# PiHatSandwich-v1.net
KiCad netlist of a schematic drawn in EAGLE
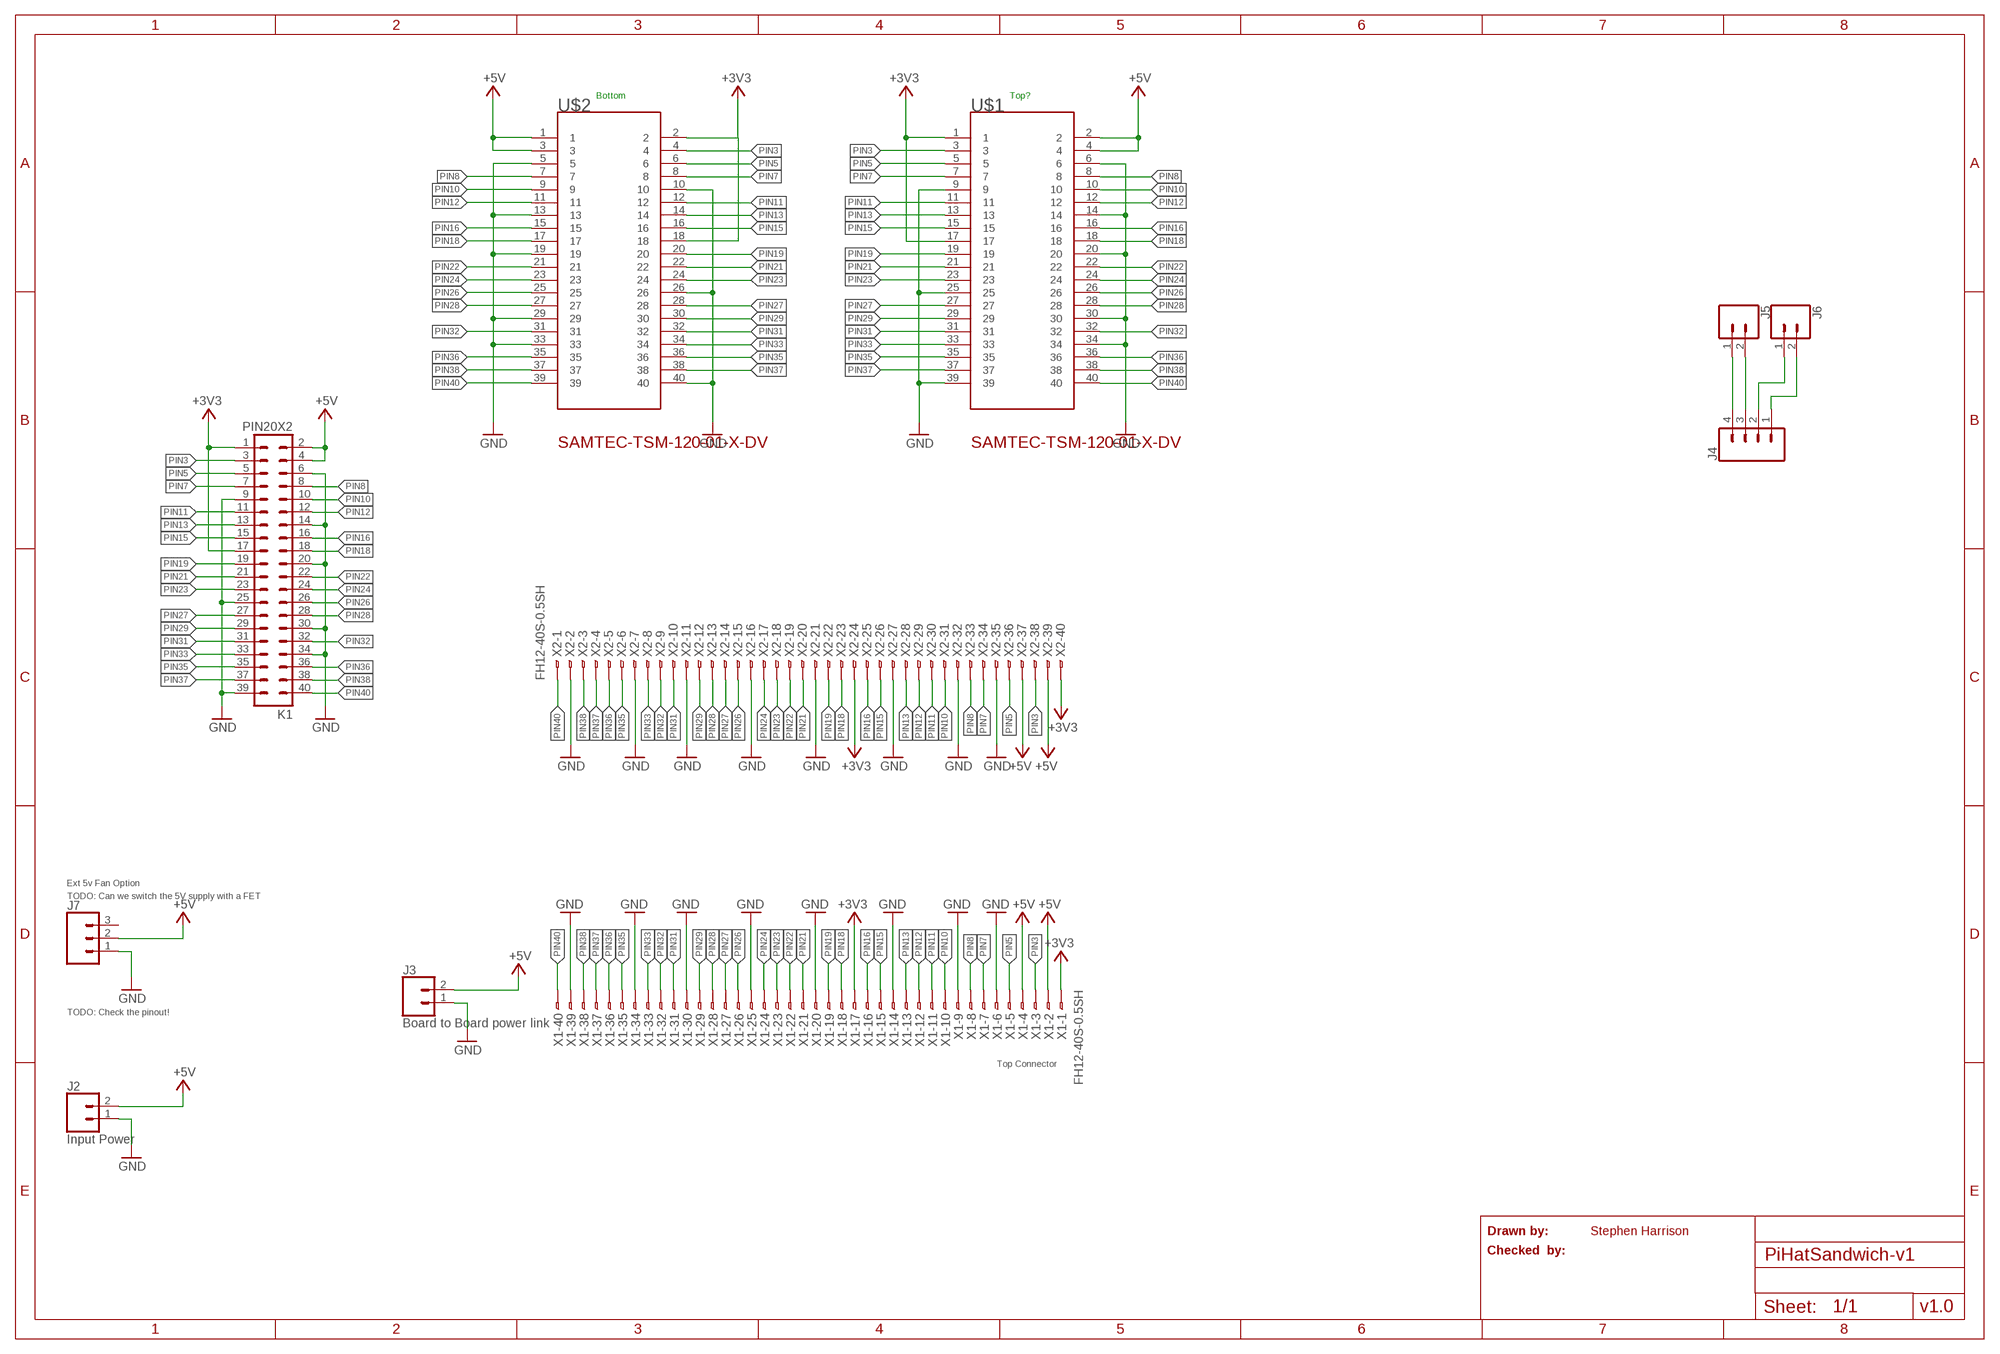
[diagram p0: schematic, sheet 1]

(export (version "E")
  (design (tool "Eeschema 10.0.6"))
  (components
    (comp (ref "J2")
      (value "Input Power")
      (footprint "eagle-import:MOLEX-1X2")
      (libsource (lib "eagle-import") (part "CONN_02POLAR"))
    )
    (comp (ref "J3")
      (value "Board to Board power link")
      (footprint "eagle-import:MOLEX-1X2")
      (libsource (lib "eagle-import") (part "CONN_02POLAR"))
    )
    (comp (ref "J4")
      (value "CONN_04POLAR")
      (footprint "eagle-import:MOLEX-1X4")
      (libsource (lib "eagle-import") (part "CONN_04POLAR"))
    )
    (comp (ref "J5")
      (value "CONN_02")
      (footprint "eagle-import:1X02")
      (libsource (lib "eagle-import") (part "CONN_02"))
    )
    (comp (ref "J6")
      (value "CONN_02")
      (footprint "eagle-import:1X02")
      (libsource (lib "eagle-import") (part "CONN_02"))
    )
    (comp (ref "J7")
      (value "CONN_03POLAR")
      (footprint "eagle-import:MOLEX-1X3")
      (libsource (lib "eagle-import") (part "CONN_03POLAR"))
    )
    (comp (ref "K1")
      (value "PIN20X2")
      (footprint "eagle-import:PIN_20X2")
      (libsource (lib "eagle-import") (part "PIN20X2"))
    )
    (comp (ref "U$1")
      (value "SAMTEC-TSM-120-01-X-DVJ")
      (footprint "eagle-import:SAMTEC-TSM-120-01-X-DV")
      (fields (field (name "MF") "Samtec") (field (name "MP") "TSM-120-01-S-DV-M"))
      (libsource (lib "eagle-import") (part "SAMTEC-TSM-120-01-X-DVJ"))
    )
    (comp (ref "U$2")
      (value "SAMTEC-TSM-120-01-X-DVJ")
      (footprint "eagle-import:SAMTEC-TSM-120-01-X-DV")
      (fields (field (name "MF") "Samtec") (field (name "MP") "TSM-120-01-S-DV-M"))
      (libsource (lib "eagle-import") (part "SAMTEC-TSM-120-01-X-DVJ"))
    )
    (comp (ref "X1")
      (value "FH12-40S-0.5SH")
      (footprint "eagle-import:FH12-40S-0.5SH")
      (fields (field (name "MPN") "FH12-40S-0.5SH(55)"))
      (libsource (lib "eagle-import") (part "FH12-40S-0.5SH"))
    )
    (comp (ref "X2")
      (value "FH12-40S-0.5SH")
      (footprint "eagle-import:FH12-40S-0.5SH")
      (fields (field (name "MPN") "FH12-40S-0.5SH(55)"))
      (libsource (lib "eagle-import") (part "FH12-40S-0.5SH"))
    )
  )
  (nets
    (net (code "1") (name "+3V3") (class "Default")
      (node (ref "K1") (pin "1") (pinfunction "1_1") (pintype "passive"))
      (node (ref "K1") (pin "17") (pinfunction "17_17") (pintype "passive"))
      (node (ref "U$1") (pin "1") (pinfunction "1_1") (pintype "passive"))
      (node (ref "U$1") (pin "17") (pinfunction "17_17") (pintype "passive"))
      (node (ref "U$2") (pin "18") (pinfunction "18_18") (pintype "passive"))
      (node (ref "U$2") (pin "2") (pinfunction "2_2") (pintype "passive"))
      (node (ref "X1") (pin "1") (pinfunction "1_1") (pintype "passive"))
      (node (ref "X1") (pin "17") (pinfunction "1_17") (pintype "passive"))
      (node (ref "X2") (pin "24") (pinfunction "1_24") (pintype "passive"))
      (node (ref "X2") (pin "40") (pinfunction "1_40") (pintype "passive"))
    )
    (net (code "2") (name "+5V") (class "Default")
      (node (ref "J2") (pin "2") (pinfunction "2_2") (pintype "passive"))
      (node (ref "J3") (pin "2") (pinfunction "2_2") (pintype "passive"))
      (node (ref "J7") (pin "2") (pinfunction "2_2") (pintype "passive"))
      (node (ref "K1") (pin "2") (pinfunction "2_2") (pintype "passive"))
      (node (ref "K1") (pin "4") (pinfunction "4_4") (pintype "passive"))
      (node (ref "U$1") (pin "2") (pinfunction "2_2") (pintype "passive"))
      (node (ref "U$1") (pin "4") (pinfunction "4_4") (pintype "passive"))
      (node (ref "U$2") (pin "1") (pinfunction "1_1") (pintype "passive"))
      (node (ref "U$2") (pin "3") (pinfunction "3_3") (pintype "passive"))
      (node (ref "X1") (pin "2") (pinfunction "1_2") (pintype "passive"))
      (node (ref "X1") (pin "4") (pinfunction "1_4") (pintype "passive"))
      (node (ref "X2") (pin "37") (pinfunction "1_37") (pintype "passive"))
      (node (ref "X2") (pin "39") (pinfunction "1_39") (pintype "passive"))
    )
    (net (code "3") (name "GND") (class "Default")
      (node (ref "J2") (pin "1") (pinfunction "1_1") (pintype "passive"))
      (node (ref "J3") (pin "1") (pinfunction "1_1") (pintype "passive"))
      (node (ref "J7") (pin "1") (pinfunction "1_1") (pintype "passive"))
      (node (ref "K1") (pin "14") (pinfunction "14_14") (pintype "passive"))
      (node (ref "K1") (pin "20") (pinfunction "20_20") (pintype "passive"))
      (node (ref "K1") (pin "25") (pinfunction "25_25") (pintype "passive"))
      (node (ref "K1") (pin "30") (pinfunction "30_30") (pintype "passive"))
      (node (ref "K1") (pin "34") (pinfunction "34_34") (pintype "passive"))
      (node (ref "K1") (pin "39") (pinfunction "39_39") (pintype "passive"))
      (node (ref "K1") (pin "6") (pinfunction "6_6") (pintype "passive"))
      (node (ref "K1") (pin "9") (pinfunction "9_9") (pintype "passive"))
      (node (ref "U$1") (pin "14") (pinfunction "14_14") (pintype "passive"))
      (node (ref "U$1") (pin "20") (pinfunction "20_20") (pintype "passive"))
      (node (ref "U$1") (pin "25") (pinfunction "25_25") (pintype "passive"))
      (node (ref "U$1") (pin "30") (pinfunction "30_30") (pintype "passive"))
      (node (ref "U$1") (pin "34") (pinfunction "34_34") (pintype "passive"))
      (node (ref "U$1") (pin "39") (pinfunction "39_39") (pintype "passive"))
      (node (ref "U$1") (pin "6") (pinfunction "6_6") (pintype "passive"))
      (node (ref "U$1") (pin "9") (pinfunction "9_9") (pintype "passive"))
      (node (ref "U$2") (pin "10") (pinfunction "10_10") (pintype "passive"))
      (node (ref "U$2") (pin "13") (pinfunction "13_13") (pintype "passive"))
      (node (ref "U$2") (pin "19") (pinfunction "19_19") (pintype "passive"))
      (node (ref "U$2") (pin "26") (pinfunction "26_26") (pintype "passive"))
      (node (ref "U$2") (pin "29") (pinfunction "29_29") (pintype "passive"))
      (node (ref "U$2") (pin "33") (pinfunction "33_33") (pintype "passive"))
      (node (ref "U$2") (pin "40") (pinfunction "40_40") (pintype "passive"))
      (node (ref "U$2") (pin "5") (pinfunction "5_5") (pintype "passive"))
      (node (ref "X1") (pin "14") (pinfunction "1_14") (pintype "passive"))
      (node (ref "X1") (pin "20") (pinfunction "1_20") (pintype "passive"))
      (node (ref "X1") (pin "25") (pinfunction "1_25") (pintype "passive"))
      (node (ref "X1") (pin "30") (pinfunction "1_30") (pintype "passive"))
      (node (ref "X1") (pin "34") (pinfunction "1_34") (pintype "passive"))
      (node (ref "X1") (pin "39") (pinfunction "1_39") (pintype "passive"))
      (node (ref "X1") (pin "6") (pinfunction "1_6") (pintype "passive"))
      (node (ref "X1") (pin "9") (pinfunction "1_9") (pintype "passive"))
      (node (ref "X2") (pin "11") (pinfunction "1_11") (pintype "passive"))
      (node (ref "X2") (pin "16") (pinfunction "1_16") (pintype "passive"))
      (node (ref "X2") (pin "2") (pinfunction "1_2") (pintype "passive"))
      (node (ref "X2") (pin "21") (pinfunction "1_21") (pintype "passive"))
      (node (ref "X2") (pin "27") (pinfunction "1_27") (pintype "passive"))
      (node (ref "X2") (pin "32") (pinfunction "1_32") (pintype "passive"))
      (node (ref "X2") (pin "35") (pinfunction "1_35") (pintype "passive"))
      (node (ref "X2") (pin "7") (pinfunction "1_7") (pintype "passive"))
    )
    (net (code "4") (name "Net-(J4-Pad1)") (class "Default")
      (node (ref "J4") (pin "1") (pinfunction "1_1") (pintype "passive"))
      (node (ref "J6") (pin "2") (pinfunction "2_2") (pintype "passive"))
    )
    (net (code "5") (name "Net-(J4-Pad2)") (class "Default")
      (node (ref "J4") (pin "2") (pinfunction "2_2") (pintype "passive"))
      (node (ref "J6") (pin "1") (pinfunction "1_1") (pintype "passive"))
    )
    (net (code "6") (name "Net-(J4-Pad3)") (class "Default")
      (node (ref "J4") (pin "3") (pinfunction "3_3") (pintype "passive"))
      (node (ref "J5") (pin "2") (pinfunction "2_2") (pintype "passive"))
    )
    (net (code "7") (name "Net-(J4-Pad4)") (class "Default")
      (node (ref "J4") (pin "4") (pinfunction "4_4") (pintype "passive"))
      (node (ref "J5") (pin "1") (pinfunction "1_1") (pintype "passive"))
    )
    (net (code "8") (name "PIN3") (class "Default")
      (node (ref "K1") (pin "3") (pinfunction "3_3") (pintype "passive"))
      (node (ref "U$1") (pin "3") (pinfunction "3_3") (pintype "passive"))
      (node (ref "U$2") (pin "4") (pinfunction "4_4") (pintype "passive"))
      (node (ref "X1") (pin "3") (pinfunction "1_3") (pintype "passive"))
      (node (ref "X2") (pin "38") (pinfunction "1_38") (pintype "passive"))
    )
    (net (code "9") (name "PIN5") (class "Default")
      (node (ref "K1") (pin "5") (pinfunction "5_5") (pintype "passive"))
      (node (ref "U$1") (pin "5") (pinfunction "5_5") (pintype "passive"))
      (node (ref "U$2") (pin "6") (pinfunction "6_6") (pintype "passive"))
      (node (ref "X1") (pin "5") (pinfunction "1_5") (pintype "passive"))
      (node (ref "X2") (pin "36") (pinfunction "1_36") (pintype "passive"))
    )
    (net (code "10") (name "PIN7") (class "Default")
      (node (ref "K1") (pin "7") (pinfunction "7_7") (pintype "passive"))
      (node (ref "U$1") (pin "7") (pinfunction "7_7") (pintype "passive"))
      (node (ref "U$2") (pin "8") (pinfunction "8_8") (pintype "passive"))
      (node (ref "X1") (pin "7") (pinfunction "1_7") (pintype "passive"))
      (node (ref "X2") (pin "34") (pinfunction "1_34") (pintype "passive"))
    )
    (net (code "11") (name "PIN8") (class "Default")
      (node (ref "K1") (pin "8") (pinfunction "8_8") (pintype "passive"))
      (node (ref "U$1") (pin "8") (pinfunction "8_8") (pintype "passive"))
      (node (ref "U$2") (pin "7") (pinfunction "7_7") (pintype "passive"))
      (node (ref "X1") (pin "8") (pinfunction "1_8") (pintype "passive"))
      (node (ref "X2") (pin "33") (pinfunction "1_33") (pintype "passive"))
    )
    (net (code "12") (name "PIN10") (class "Default")
      (node (ref "K1") (pin "10") (pinfunction "10_10") (pintype "passive"))
      (node (ref "U$1") (pin "10") (pinfunction "10_10") (pintype "passive"))
      (node (ref "U$2") (pin "9") (pinfunction "9_9") (pintype "passive"))
      (node (ref "X1") (pin "10") (pinfunction "1_10") (pintype "passive"))
      (node (ref "X2") (pin "31") (pinfunction "1_31") (pintype "passive"))
    )
    (net (code "13") (name "PIN11") (class "Default")
      (node (ref "K1") (pin "11") (pinfunction "11_11") (pintype "passive"))
      (node (ref "U$1") (pin "11") (pinfunction "11_11") (pintype "passive"))
      (node (ref "U$2") (pin "12") (pinfunction "12_12") (pintype "passive"))
      (node (ref "X1") (pin "11") (pinfunction "1_11") (pintype "passive"))
      (node (ref "X2") (pin "30") (pinfunction "1_30") (pintype "passive"))
    )
    (net (code "14") (name "PIN12") (class "Default")
      (node (ref "K1") (pin "12") (pinfunction "12_12") (pintype "passive"))
      (node (ref "U$1") (pin "12") (pinfunction "12_12") (pintype "passive"))
      (node (ref "U$2") (pin "11") (pinfunction "11_11") (pintype "passive"))
      (node (ref "X1") (pin "12") (pinfunction "1_12") (pintype "passive"))
      (node (ref "X2") (pin "29") (pinfunction "1_29") (pintype "passive"))
    )
    (net (code "15") (name "PIN13") (class "Default")
      (node (ref "K1") (pin "13") (pinfunction "13_13") (pintype "passive"))
      (node (ref "U$1") (pin "13") (pinfunction "13_13") (pintype "passive"))
      (node (ref "U$2") (pin "14") (pinfunction "14_14") (pintype "passive"))
      (node (ref "X1") (pin "13") (pinfunction "1_13") (pintype "passive"))
      (node (ref "X2") (pin "28") (pinfunction "1_28") (pintype "passive"))
    )
    (net (code "16") (name "PIN15") (class "Default")
      (node (ref "K1") (pin "15") (pinfunction "15_15") (pintype "passive"))
      (node (ref "U$1") (pin "15") (pinfunction "15_15") (pintype "passive"))
      (node (ref "U$2") (pin "16") (pinfunction "16_16") (pintype "passive"))
      (node (ref "X1") (pin "15") (pinfunction "1_15") (pintype "passive"))
      (node (ref "X2") (pin "26") (pinfunction "1_26") (pintype "passive"))
    )
    (net (code "17") (name "PIN16") (class "Default")
      (node (ref "K1") (pin "16") (pinfunction "16_16") (pintype "passive"))
      (node (ref "U$1") (pin "16") (pinfunction "16_16") (pintype "passive"))
      (node (ref "U$2") (pin "15") (pinfunction "15_15") (pintype "passive"))
      (node (ref "X1") (pin "16") (pinfunction "1_16") (pintype "passive"))
      (node (ref "X2") (pin "25") (pinfunction "1_25") (pintype "passive"))
    )
    (net (code "18") (name "PIN18") (class "Default")
      (node (ref "K1") (pin "18") (pinfunction "18_18") (pintype "passive"))
      (node (ref "U$1") (pin "18") (pinfunction "18_18") (pintype "passive"))
      (node (ref "U$2") (pin "17") (pinfunction "17_17") (pintype "passive"))
      (node (ref "X1") (pin "18") (pinfunction "1_18") (pintype "passive"))
      (node (ref "X2") (pin "23") (pinfunction "1_23") (pintype "passive"))
    )
    (net (code "19") (name "PIN19") (class "Default")
      (node (ref "K1") (pin "19") (pinfunction "19_19") (pintype "passive"))
      (node (ref "U$1") (pin "19") (pinfunction "19_19") (pintype "passive"))
      (node (ref "U$2") (pin "20") (pinfunction "20_20") (pintype "passive"))
      (node (ref "X1") (pin "19") (pinfunction "1_19") (pintype "passive"))
      (node (ref "X2") (pin "22") (pinfunction "1_22") (pintype "passive"))
    )
    (net (code "20") (name "PIN21") (class "Default")
      (node (ref "K1") (pin "21") (pinfunction "21_21") (pintype "passive"))
      (node (ref "U$1") (pin "21") (pinfunction "21_21") (pintype "passive"))
      (node (ref "U$2") (pin "22") (pinfunction "22_22") (pintype "passive"))
      (node (ref "X1") (pin "21") (pinfunction "1_21") (pintype "passive"))
      (node (ref "X2") (pin "20") (pinfunction "1_20") (pintype "passive"))
    )
    (net (code "21") (name "PIN22") (class "Default")
      (node (ref "K1") (pin "22") (pinfunction "22_22") (pintype "passive"))
      (node (ref "U$1") (pin "22") (pinfunction "22_22") (pintype "passive"))
      (node (ref "U$2") (pin "21") (pinfunction "21_21") (pintype "passive"))
      (node (ref "X1") (pin "22") (pinfunction "1_22") (pintype "passive"))
      (node (ref "X2") (pin "19") (pinfunction "1_19") (pintype "passive"))
    )
    (net (code "22") (name "PIN23") (class "Default")
      (node (ref "K1") (pin "23") (pinfunction "23_23") (pintype "passive"))
      (node (ref "U$1") (pin "23") (pinfunction "23_23") (pintype "passive"))
      (node (ref "U$2") (pin "24") (pinfunction "24_24") (pintype "passive"))
      (node (ref "X1") (pin "23") (pinfunction "1_23") (pintype "passive"))
      (node (ref "X2") (pin "18") (pinfunction "1_18") (pintype "passive"))
    )
    (net (code "23") (name "PIN24") (class "Default")
      (node (ref "K1") (pin "24") (pinfunction "24_24") (pintype "passive"))
      (node (ref "U$1") (pin "24") (pinfunction "24_24") (pintype "passive"))
      (node (ref "U$2") (pin "23") (pinfunction "23_23") (pintype "passive"))
      (node (ref "X1") (pin "24") (pinfunction "1_24") (pintype "passive"))
      (node (ref "X2") (pin "17") (pinfunction "1_17") (pintype "passive"))
    )
    (net (code "24") (name "PIN26") (class "Default")
      (node (ref "K1") (pin "26") (pinfunction "26_26") (pintype "passive"))
      (node (ref "U$1") (pin "26") (pinfunction "26_26") (pintype "passive"))
      (node (ref "U$2") (pin "25") (pinfunction "25_25") (pintype "passive"))
      (node (ref "X1") (pin "26") (pinfunction "1_26") (pintype "passive"))
      (node (ref "X2") (pin "15") (pinfunction "1_15") (pintype "passive"))
    )
    (net (code "25") (name "PIN27") (class "Default")
      (node (ref "K1") (pin "27") (pinfunction "27_27") (pintype "passive"))
      (node (ref "U$1") (pin "27") (pinfunction "27_27") (pintype "passive"))
      (node (ref "U$2") (pin "28") (pinfunction "28_28") (pintype "passive"))
      (node (ref "X1") (pin "27") (pinfunction "1_27") (pintype "passive"))
      (node (ref "X2") (pin "14") (pinfunction "1_14") (pintype "passive"))
    )
    (net (code "26") (name "PIN28") (class "Default")
      (node (ref "K1") (pin "28") (pinfunction "28_28") (pintype "passive"))
      (node (ref "U$1") (pin "28") (pinfunction "28_28") (pintype "passive"))
      (node (ref "U$2") (pin "27") (pinfunction "27_27") (pintype "passive"))
      (node (ref "X1") (pin "28") (pinfunction "1_28") (pintype "passive"))
      (node (ref "X2") (pin "13") (pinfunction "1_13") (pintype "passive"))
    )
    (net (code "27") (name "PIN29") (class "Default")
      (node (ref "K1") (pin "29") (pinfunction "29_29") (pintype "passive"))
      (node (ref "U$1") (pin "29") (pinfunction "29_29") (pintype "passive"))
      (node (ref "U$2") (pin "30") (pinfunction "30_30") (pintype "passive"))
      (node (ref "X1") (pin "29") (pinfunction "1_29") (pintype "passive"))
      (node (ref "X2") (pin "12") (pinfunction "1_12") (pintype "passive"))
    )
    (net (code "28") (name "PIN31") (class "Default")
      (node (ref "K1") (pin "31") (pinfunction "31_31") (pintype "passive"))
      (node (ref "U$1") (pin "31") (pinfunction "31_31") (pintype "passive"))
      (node (ref "U$2") (pin "32") (pinfunction "32_32") (pintype "passive"))
      (node (ref "X1") (pin "31") (pinfunction "1_31") (pintype "passive"))
      (node (ref "X2") (pin "10") (pinfunction "1_10") (pintype "passive"))
    )
    (net (code "29") (name "PIN32") (class "Default")
      (node (ref "K1") (pin "32") (pinfunction "32_32") (pintype "passive"))
      (node (ref "U$1") (pin "32") (pinfunction "32_32") (pintype "passive"))
      (node (ref "U$2") (pin "31") (pinfunction "31_31") (pintype "passive"))
      (node (ref "X1") (pin "32") (pinfunction "1_32") (pintype "passive"))
      (node (ref "X2") (pin "9") (pinfunction "1_9") (pintype "passive"))
    )
    (net (code "30") (name "PIN33") (class "Default")
      (node (ref "K1") (pin "33") (pinfunction "33_33") (pintype "passive"))
      (node (ref "U$1") (pin "33") (pinfunction "33_33") (pintype "passive"))
      (node (ref "U$2") (pin "34") (pinfunction "34_34") (pintype "passive"))
      (node (ref "X1") (pin "33") (pinfunction "1_33") (pintype "passive"))
      (node (ref "X2") (pin "8") (pinfunction "1_8") (pintype "passive"))
    )
    (net (code "31") (name "PIN35") (class "Default")
      (node (ref "K1") (pin "35") (pinfunction "35_35") (pintype "passive"))
      (node (ref "U$1") (pin "35") (pinfunction "35_35") (pintype "passive"))
      (node (ref "U$2") (pin "36") (pinfunction "36_36") (pintype "passive"))
      (node (ref "X1") (pin "35") (pinfunction "1_35") (pintype "passive"))
      (node (ref "X2") (pin "6") (pinfunction "1_6") (pintype "passive"))
    )
    (net (code "32") (name "PIN36") (class "Default")
      (node (ref "K1") (pin "36") (pinfunction "36_36") (pintype "passive"))
      (node (ref "U$1") (pin "36") (pinfunction "36_36") (pintype "passive"))
      (node (ref "U$2") (pin "35") (pinfunction "35_35") (pintype "passive"))
      (node (ref "X1") (pin "36") (pinfunction "1_36") (pintype "passive"))
      (node (ref "X2") (pin "5") (pinfunction "1_5") (pintype "passive"))
    )
    (net (code "33") (name "PIN37") (class "Default")
      (node (ref "K1") (pin "37") (pinfunction "37_37") (pintype "passive"))
      (node (ref "U$1") (pin "37") (pinfunction "37_37") (pintype "passive"))
      (node (ref "U$2") (pin "38") (pinfunction "38_38") (pintype "passive"))
      (node (ref "X1") (pin "37") (pinfunction "1_37") (pintype "passive"))
      (node (ref "X2") (pin "4") (pinfunction "1_4") (pintype "passive"))
    )
    (net (code "34") (name "PIN38") (class "Default")
      (node (ref "K1") (pin "38") (pinfunction "38_38") (pintype "passive"))
      (node (ref "U$1") (pin "38") (pinfunction "38_38") (pintype "passive"))
      (node (ref "U$2") (pin "37") (pinfunction "37_37") (pintype "passive"))
      (node (ref "X1") (pin "38") (pinfunction "1_38") (pintype "passive"))
      (node (ref "X2") (pin "3") (pinfunction "1_3") (pintype "passive"))
    )
    (net (code "35") (name "PIN40") (class "Default")
      (node (ref "K1") (pin "40") (pinfunction "40_40") (pintype "passive"))
      (node (ref "U$1") (pin "40") (pinfunction "40_40") (pintype "passive"))
      (node (ref "U$2") (pin "39") (pinfunction "39_39") (pintype "passive"))
      (node (ref "X1") (pin "40") (pinfunction "1_40") (pintype "passive"))
      (node (ref "X2") (pin "1") (pinfunction "1_1") (pintype "passive"))
    )
    (net (code "36") (name "unconnected-(J7-Pad3)") (class "Default")
      (node (ref "J7") (pin "3") (pinfunction "3_3") (pintype "passive"))
    )
  )
)
